# Fri3D_IRA_Peripherals.net
KiCad netlist of a schematic drawn in Altium Designer
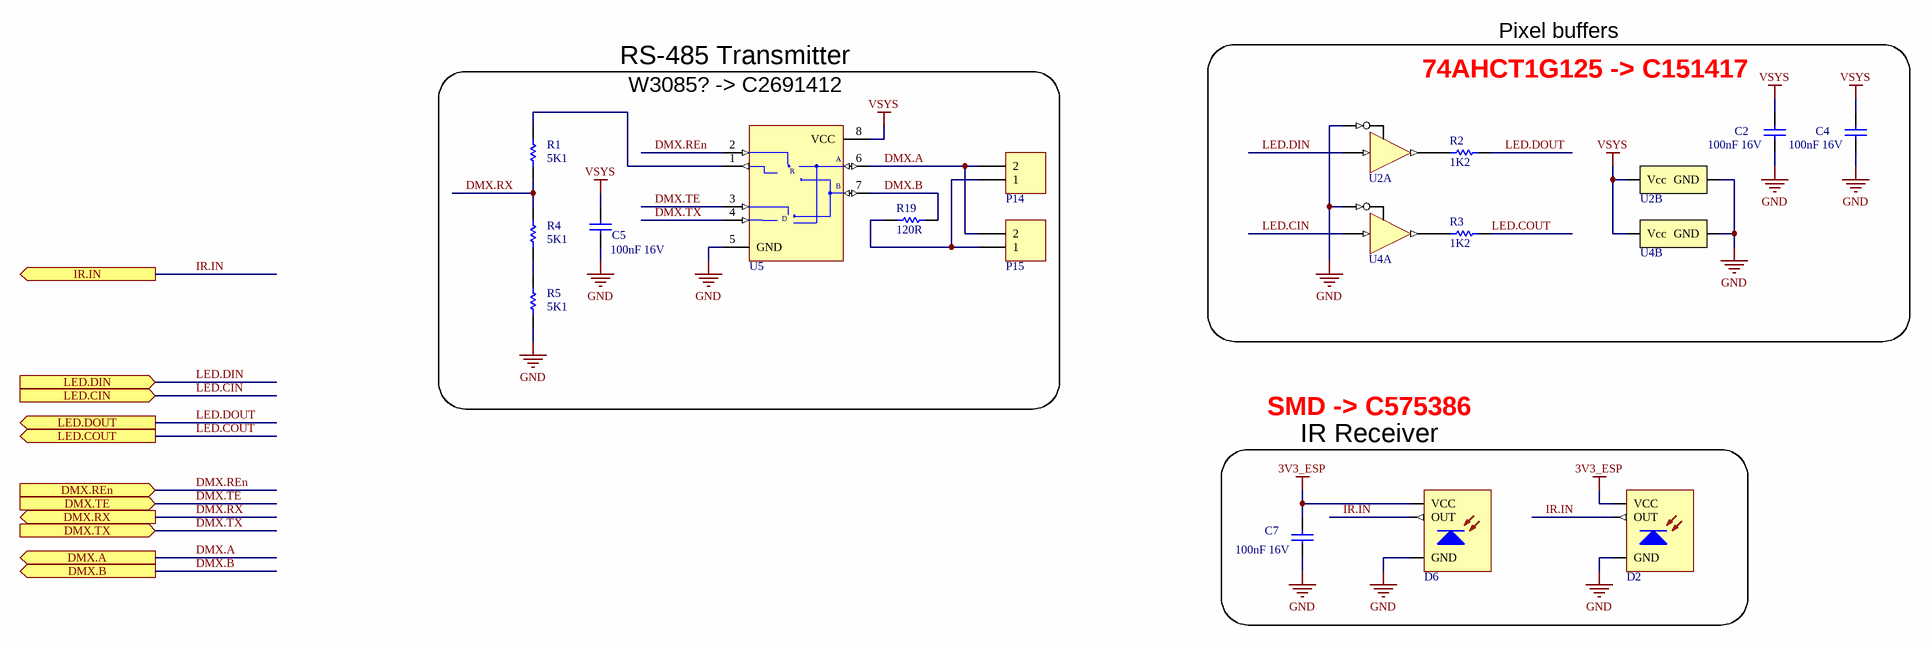
[diagram p0: Fri3D_IRA_Peripherals.SchDoc]

(export (version "E")
  (design (tool "Eeschema 10.0.6"))
  (components
    (comp (ref "C2")
      (value "100nF 16V")
      (footprint "C0603_N")
      (description "Capacitor Ceramic")
      (libsource (lib "Phyx_Components") (part "CAP_CERAMIC"))
    )
    (comp (ref "C4")
      (value "100nF 16V")
      (footprint "C0603_N")
      (description "Capacitor Ceramic")
      (libsource (lib "Phyx_Components") (part "CAP_CERAMIC"))
    )
    (comp (ref "C5")
      (value "100nF 16V")
      (footprint "C0603_N")
      (description "Capacitor Ceramic")
      (libsource (lib "Phyx_Components") (part "CAP_CERAMIC"))
    )
    (comp (ref "C7")
      (value "100nF 16V")
      (footprint "C0603_N")
      (description "Capacitor Ceramic")
      (libsource (lib "Phyx_Components") (part "CAP_CERAMIC"))
    )
    (comp (ref "D2")
      (value "ZIRM-5042B-42-Z2 Infrared Receiver 38 kHz 45° 2.7-5.5V 940nm")
      (footprint "CHAU_ZIRM-5042B-42-Z2")
      (description "=Description")
      (libsource (lib "Phyx_Components") (part "PHO_IR_TSOP381x"))
    )
    (comp (ref "D6")
      (value "IRM-3638N3F14 Infrared Receiver 38 kHz 45° 2.7-5.5V")
      (footprint "VIS_TSOP381x_BENT")
      (description "=Description")
      (libsource (lib "Phyx_Components") (part "PHO_IR_TSOP381x"))
    )
    (comp (ref "P14")
      (value "Easy to solder connection")
      (footprint "SOLDER_SW_V_1MM")
      (libsource (lib "Phyx_Components") (part "Header 2"))
    )
    (comp (ref "P15")
      (value "Header 2")
      (footprint "HDR1X2")
      (libsource (lib "Phyx_Components") (part "Header 2"))
    )
    (comp (ref "R1")
      (value "5K1")
      (footprint "R0603_N")
      (fields (field (name "Comment") "RESISTOR"))
      (libsource (lib "Phyx_Components") (part "RESISTOR"))
    )
    (comp (ref "R2")
      (value "1K2")
      (footprint "R0603_N")
      (fields (field (name "Comment") "RESISTOR"))
      (libsource (lib "Phyx_Components") (part "RESISTOR"))
    )
    (comp (ref "R3")
      (value "1K2")
      (footprint "R0603_N")
      (fields (field (name "Comment") "RESISTOR"))
      (libsource (lib "Phyx_Components") (part "RESISTOR"))
    )
    (comp (ref "R4")
      (value "5K1")
      (footprint "R0603_N")
      (fields (field (name "Comment") "RESISTOR"))
      (libsource (lib "Phyx_Components") (part "RESISTOR"))
    )
    (comp (ref "R5")
      (value "5K1")
      (footprint "R0603_N")
      (fields (field (name "Comment") "RESISTOR"))
      (libsource (lib "Phyx_Components") (part "RESISTOR"))
    )
    (comp (ref "R19")
      (value "120R")
      (footprint "R1206")
      (fields (field (name "Comment") "RESISTOR"))
      (libsource (lib "Phyx_Components") (part "RESISTOR"))
    )
    (comp (ref "U2")
      (value "SN74AHCT1G125DCKR  Buffer, Tri-State, 4.5V to 5.5V")
      (footprint "TI_DCK_R-PDSO-G5")
      (description "=Description")
      (libsource (lib "Phyx_Components") (part "SN74AHCT1G125"))
    )
    (comp (ref "U4")
      (value "SN74AHCT1G125DCKR  Buffer, Tri-State, 4.5V to 5.5V")
      (footprint "TI_DCK_R-PDSO-G5")
      (description "=Description")
      (libsource (lib "Phyx_Components") (part "SN74AHCT1G125"))
    )
    (comp (ref "U5")
      (value "RS-485 5V Transceiver")
      (footprint "SOIC_N_8")
      (libsource (lib "Phyx_Components") (part "MAX485"))
    )
  )
  (nets
    (net (code "1") (name "/DMX.A") (class "Default")
      (node (ref "P14") (pin "2") (pinfunction "2_2") (pintype "passive"))
      (node (ref "P15") (pin "2") (pinfunction "2_2") (pintype "passive"))
      (node (ref "U5") (pin "6") (pinfunction "A_6") (pintype "bidirectional"))
    )
    (net (code "2") (name "/DMX.B") (class "Default")
      (node (ref "R19") (pin "2") (pinfunction "2_2") (pintype "passive"))
      (node (ref "U5") (pin "7") (pinfunction "B_7") (pintype "bidirectional"))
    )
    (net (code "3") (name "/DMX.REn") (class "Default")
      (node (ref "U5") (pin "2") (pinfunction "~{RE}_2") (pintype "input"))
    )
    (net (code "4") (name "/DMX.RX") (class "Default")
      (node (ref "R1") (pin "2") (pinfunction "2_2") (pintype "passive"))
      (node (ref "R4") (pin "1") (pinfunction "1_1") (pintype "passive"))
    )
    (net (code "5") (name "/DMX.TE") (class "Default")
      (node (ref "U5") (pin "3") (pinfunction "DE_3") (pintype "input"))
    )
    (net (code "6") (name "/DMX.TX") (class "Default")
      (node (ref "U5") (pin "4") (pinfunction "DI_4") (pintype "input"))
    )
    (net (code "7") (name "/IR.IN") (class "Default")
      (node (ref "D2") (pin "1") (pinfunction "OUT_1") (pintype "output"))
      (node (ref "D6") (pin "1") (pinfunction "OUT_1") (pintype "output"))
    )
    (net (code "8") (name "/LED.CIN") (class "Default")
      (node (ref "U4") (pin "2") (pinfunction "A_2") (pintype "input"))
    )
    (net (code "9") (name "/LED.COUT") (class "Default")
      (node (ref "R3") (pin "2") (pinfunction "2_2") (pintype "passive"))
    )
    (net (code "10") (name "/LED.DIN") (class "Default")
      (node (ref "U2") (pin "2") (pinfunction "A_2") (pintype "input"))
    )
    (net (code "11") (name "/LED.DOUT") (class "Default")
      (node (ref "R2") (pin "2") (pinfunction "2_2") (pintype "passive"))
    )
    (net (code "12") (name "3V3_ESP") (class "Default")
      (node (ref "C7") (pin "1") (pinfunction "1_1") (pintype "passive"))
      (node (ref "D2") (pin "3") (pinfunction "VCC_3") (pintype "power_in"))
      (node (ref "D6") (pin "3") (pinfunction "VCC_3") (pintype "power_in"))
    )
    (net (code "13") (name "GND") (class "Default")
      (node (ref "C2") (pin "2") (pinfunction "2_2") (pintype "passive"))
      (node (ref "C4") (pin "2") (pinfunction "2_2") (pintype "passive"))
      (node (ref "C5") (pin "2") (pinfunction "2_2") (pintype "passive"))
      (node (ref "C7") (pin "2") (pinfunction "2_2") (pintype "passive"))
      (node (ref "D2") (pin "2") (pinfunction "GND_2") (pintype "power_in"))
      (node (ref "D6") (pin "2") (pinfunction "GND_2") (pintype "power_in"))
      (node (ref "R5") (pin "2") (pinfunction "2_2") (pintype "passive"))
      (node (ref "U2") (pin "1") (pinfunction "~{OE}_1") (pintype "input"))
      (node (ref "U2") (pin "3") (pinfunction "GND_3") (pintype "power_in"))
      (node (ref "U4") (pin "1") (pinfunction "~{OE}_1") (pintype "input"))
      (node (ref "U4") (pin "3") (pinfunction "GND_3") (pintype "power_in"))
      (node (ref "U5") (pin "5") (pinfunction "GND_5") (pintype "power_in"))
    )
    (net (code "14") (name "Net-(P14-Pad1)") (class "Default")
      (node (ref "P14") (pin "1") (pinfunction "1_1") (pintype "passive"))
      (node (ref "P15") (pin "1") (pinfunction "1_1") (pintype "passive"))
      (node (ref "R19") (pin "1") (pinfunction "1_1") (pintype "passive"))
    )
    (net (code "15") (name "Net-(R4-Pad2)") (class "Default")
      (node (ref "R4") (pin "2") (pinfunction "2_2") (pintype "passive"))
      (node (ref "R5") (pin "1") (pinfunction "1_1") (pintype "passive"))
    )
    (net (code "16") (name "Net-(U2A-Y)") (class "Default")
      (node (ref "R2") (pin "1") (pinfunction "1_1") (pintype "passive"))
      (node (ref "U2") (pin "4") (pinfunction "Y_4") (pintype "output"))
    )
    (net (code "17") (name "Net-(U4A-Y)") (class "Default")
      (node (ref "R3") (pin "1") (pinfunction "1_1") (pintype "passive"))
      (node (ref "U4") (pin "4") (pinfunction "Y_4") (pintype "output"))
    )
    (net (code "18") (name "Net-(U5-RO)") (class "Default")
      (node (ref "R1") (pin "1") (pinfunction "1_1") (pintype "passive"))
      (node (ref "U5") (pin "1") (pinfunction "RO_1") (pintype "output"))
    )
    (net (code "19") (name "VSYS") (class "Default")
      (node (ref "C2") (pin "1") (pinfunction "1_1") (pintype "passive"))
      (node (ref "C4") (pin "1") (pinfunction "1_1") (pintype "passive"))
      (node (ref "C5") (pin "1") (pinfunction "1_1") (pintype "passive"))
      (node (ref "U2") (pin "5") (pinfunction "Vcc_5") (pintype "power_in"))
      (node (ref "U4") (pin "5") (pinfunction "Vcc_5") (pintype "power_in"))
      (node (ref "U5") (pin "8") (pinfunction "VCC_8") (pintype "power_in"))
    )
  )
)
